# ControlBoardMain.net
KiCad netlist of a schematic drawn in EAGLE
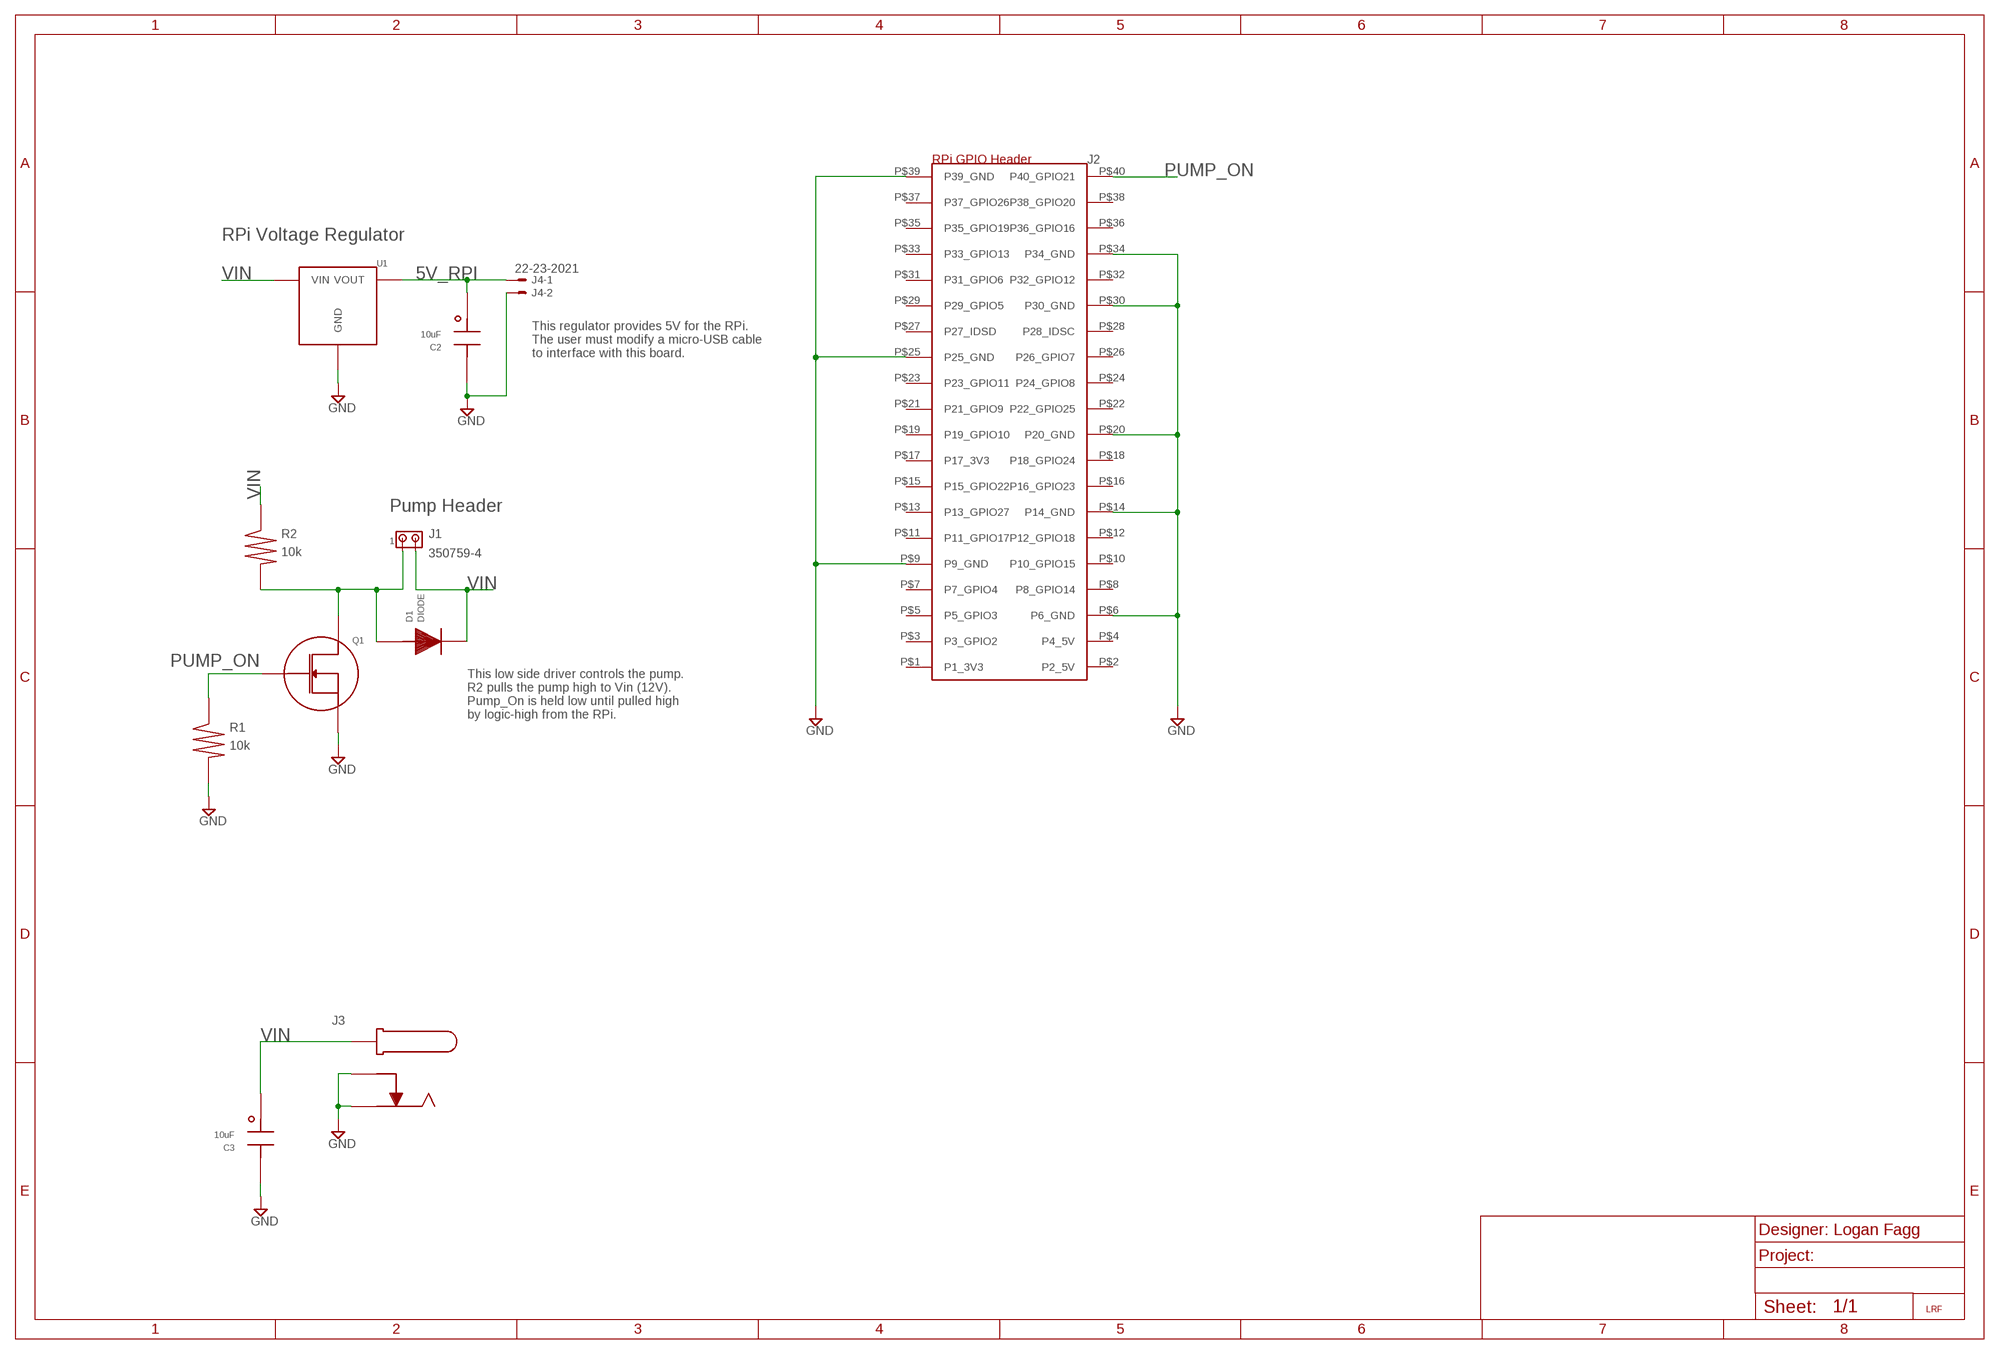
[diagram p0: schematic, sheet 1]

(export (version "E")
  (design (tool "Eeschema 10.0.6"))
  (components
    (comp (ref "C2")
      (value "10uF")
      (footprint "eagle-import:TH_PASSIVE")
      (libsource (lib "eagle-import") (part "CAPACITOR"))
    )
    (comp (ref "C3")
      (value "10uF")
      (footprint "eagle-import:TH_PASSIVE")
      (libsource (lib "eagle-import") (part "CAPACITOR"))
    )
    (comp (ref "D1")
      (value "DIODE")
      (footprint "eagle-import:TH_PASSIVE")
      (libsource (lib "eagle-import") (part "DIODE"))
    )
    (comp (ref "J1")
      (value "350759-4")
      (footprint "eagle-import:350759-4")
      (libsource (lib "eagle-import") (part "350759-4"))
    )
    (comp (ref "J2")
      (value "RPI_HEADER")
      (footprint "eagle-import:RPIHEADER")
      (libsource (lib "eagle-import") (part "RPI_HEADER"))
    )
    (comp (ref "J3")
      (value "DC_POWERJACK")
      (footprint "eagle-import:DC_POWERJACK")
      (libsource (lib "eagle-import") (part "DC_POWERJACK"))
    )
    (comp (ref "J4")
      (value "22-23-2021")
      (footprint "eagle-import:22-23-2021")
      (fields (field (name "MF") "MOLEX"))
      (libsource (lib "eagle-import") (part "22-23-2021"))
    )
    (comp (ref "Q1")
      (value "NMOS")
      (footprint "eagle-import:TH_3PIN")
      (libsource (lib "eagle-import") (part "NMOS"))
    )
    (comp (ref "R1")
      (value "10k")
      (footprint "eagle-import:TH_PASSIVE")
      (libsource (lib "eagle-import") (part "RESISTOR"))
    )
    (comp (ref "R2")
      (value "10k")
      (footprint "eagle-import:TH_PASSIVE")
      (libsource (lib "eagle-import") (part "RESISTOR"))
    )
    (comp (ref "U$1")
      (value "LOGO")
      (footprint "eagle-import:LOGO")
      (libsource (lib "eagle-import") (part "LOGO"))
    )
    (comp (ref "U1")
      (value "VOLTAGE_REGULATOR")
      (footprint "eagle-import:TH_3PIN")
      (libsource (lib "eagle-import") (part "VOLTAGE_REGULATOR"))
    )
  )
  (nets
    (net (code "1") (name "/5V_RPI") (class "Default")
      (node (ref "C2") (pin "P1") (pinfunction "P1_P1") (pintype "bidirectional"))
      (node (ref "J4") (pin "1") (pinfunction "S_1") (pintype "passive"))
      (node (ref "U1") (pin "P3") (pinfunction "VOUT_P3") (pintype "bidirectional"))
    )
    (net (code "2") (name "/PUMP_ON") (class "Default")
      (node (ref "J2") (pin "P$40") (pinfunction "P40_GPIO21_P$40") (pintype "bidirectional"))
      (node (ref "Q1") (pin "P1") (pinfunction "GATE_P1") (pintype "bidirectional"))
      (node (ref "R1") (pin "P1") (pinfunction "P1_P1") (pintype "bidirectional"))
    )
    (net (code "3") (name "/VIN") (class "Default")
      (node (ref "C3") (pin "P1") (pinfunction "P1_P1") (pintype "bidirectional"))
      (node (ref "D1") (pin "P1") (pinfunction "P1_P1") (pintype "bidirectional"))
      (node (ref "J1") (pin "2") (pinfunction "2_2") (pintype "passive"))
      (node (ref "J3") (pin "P1") (pinfunction "P1_P1") (pintype "bidirectional"))
      (node (ref "R2") (pin "P1") (pinfunction "P1_P1") (pintype "bidirectional"))
      (node (ref "U1") (pin "P1") (pinfunction "VIN_P1") (pintype "bidirectional"))
    )
    (net (code "4") (name "GND") (class "Default")
      (node (ref "C2") (pin "P2") (pinfunction "P2_P2") (pintype "bidirectional"))
      (node (ref "C3") (pin "P2") (pinfunction "P2_P2") (pintype "bidirectional"))
      (node (ref "J2") (pin "P$14") (pinfunction "P14_GND_P$14") (pintype "bidirectional"))
      (node (ref "J2") (pin "P$20") (pinfunction "P20_GND_P$20") (pintype "bidirectional"))
      (node (ref "J2") (pin "P$25") (pinfunction "P25_GND_P$25") (pintype "bidirectional"))
      (node (ref "J2") (pin "P$30") (pinfunction "P30_GND_P$30") (pintype "bidirectional"))
      (node (ref "J2") (pin "P$34") (pinfunction "P34_GND_P$34") (pintype "bidirectional"))
      (node (ref "J2") (pin "P$39") (pinfunction "P39_GND_P$39") (pintype "bidirectional"))
      (node (ref "J2") (pin "P$6") (pinfunction "P6_GND_P$6") (pintype "bidirectional"))
      (node (ref "J2") (pin "P$9") (pinfunction "P9_GND_P$9") (pintype "bidirectional"))
      (node (ref "J3") (pin "P2") (pinfunction "P2_P2") (pintype "bidirectional"))
      (node (ref "J3") (pin "P3") (pinfunction "P3_P3") (pintype "bidirectional"))
      (node (ref "J4") (pin "2") (pinfunction "S_2") (pintype "passive"))
      (node (ref "Q1") (pin "P3") (pinfunction "SOURCE_P3") (pintype "bidirectional"))
      (node (ref "R1") (pin "P2") (pinfunction "P2_P2") (pintype "bidirectional"))
      (node (ref "U1") (pin "P2") (pinfunction "GND_P2") (pintype "bidirectional"))
    )
    (net (code "5") (name "Net-(Q1-DRAIN)") (class "Default")
      (node (ref "D1") (pin "P2") (pinfunction "P2_P2") (pintype "bidirectional"))
      (node (ref "J1") (pin "1") (pinfunction "1_1") (pintype "passive"))
      (node (ref "Q1") (pin "P2") (pinfunction "DRAIN_P2") (pintype "bidirectional"))
      (node (ref "R2") (pin "P2") (pinfunction "P2_P2") (pintype "bidirectional"))
    )
    (net (code "6") (name "unconnected-(J2-P1_3V3-PadP$1)") (class "Default")
      (node (ref "J2") (pin "P$1") (pinfunction "P1_3V3_P$1") (pintype "bidirectional"))
    )
    (net (code "7") (name "unconnected-(J2-P2_5V-PadP$2)") (class "Default")
      (node (ref "J2") (pin "P$2") (pinfunction "P2_5V_P$2") (pintype "bidirectional"))
    )
    (net (code "8") (name "unconnected-(J2-P3_GPIO2-PadP$3)") (class "Default")
      (node (ref "J2") (pin "P$3") (pinfunction "P3_GPIO2_P$3") (pintype "bidirectional"))
    )
    (net (code "9") (name "unconnected-(J2-P4_5V-PadP$4)") (class "Default")
      (node (ref "J2") (pin "P$4") (pinfunction "P4_5V_P$4") (pintype "bidirectional"))
    )
    (net (code "10") (name "unconnected-(J2-P5_GPIO3-PadP$5)") (class "Default")
      (node (ref "J2") (pin "P$5") (pinfunction "P5_GPIO3_P$5") (pintype "bidirectional"))
    )
    (net (code "11") (name "unconnected-(J2-P7_GPIO4-PadP$7)") (class "Default")
      (node (ref "J2") (pin "P$7") (pinfunction "P7_GPIO4_P$7") (pintype "bidirectional"))
    )
    (net (code "12") (name "unconnected-(J2-P8_GPIO14-PadP$8)") (class "Default")
      (node (ref "J2") (pin "P$8") (pinfunction "P8_GPIO14_P$8") (pintype "bidirectional"))
    )
    (net (code "13") (name "unconnected-(J2-P10_GPIO15-PadP$10)") (class "Default")
      (node (ref "J2") (pin "P$10") (pinfunction "P10_GPIO15_P$10") (pintype "bidirectional"))
    )
    (net (code "14") (name "unconnected-(J2-P11_GPIO17-PadP$11)") (class "Default")
      (node (ref "J2") (pin "P$11") (pinfunction "P11_GPIO17_P$11") (pintype "bidirectional"))
    )
    (net (code "15") (name "unconnected-(J2-P12_GPIO18-PadP$12)") (class "Default")
      (node (ref "J2") (pin "P$12") (pinfunction "P12_GPIO18_P$12") (pintype "bidirectional"))
    )
    (net (code "16") (name "unconnected-(J2-P13_GPIO27-PadP$13)") (class "Default")
      (node (ref "J2") (pin "P$13") (pinfunction "P13_GPIO27_P$13") (pintype "bidirectional"))
    )
    (net (code "17") (name "unconnected-(J2-P15_GPIO22-PadP$15)") (class "Default")
      (node (ref "J2") (pin "P$15") (pinfunction "P15_GPIO22_P$15") (pintype "bidirectional"))
    )
    (net (code "18") (name "unconnected-(J2-P16_GPIO23-PadP$16)") (class "Default")
      (node (ref "J2") (pin "P$16") (pinfunction "P16_GPIO23_P$16") (pintype "bidirectional"))
    )
    (net (code "19") (name "unconnected-(J2-P17_3V3-PadP$17)") (class "Default")
      (node (ref "J2") (pin "P$17") (pinfunction "P17_3V3_P$17") (pintype "bidirectional"))
    )
    (net (code "20") (name "unconnected-(J2-P18_GPIO24-PadP$18)") (class "Default")
      (node (ref "J2") (pin "P$18") (pinfunction "P18_GPIO24_P$18") (pintype "bidirectional"))
    )
    (net (code "21") (name "unconnected-(J2-P19_GPIO10-PadP$19)") (class "Default")
      (node (ref "J2") (pin "P$19") (pinfunction "P19_GPIO10_P$19") (pintype "bidirectional"))
    )
    (net (code "22") (name "unconnected-(J2-P21_GPIO9-PadP$21)") (class "Default")
      (node (ref "J2") (pin "P$21") (pinfunction "P21_GPIO9_P$21") (pintype "bidirectional"))
    )
    (net (code "23") (name "unconnected-(J2-P22_GPIO25-PadP$22)") (class "Default")
      (node (ref "J2") (pin "P$22") (pinfunction "P22_GPIO25_P$22") (pintype "bidirectional"))
    )
    (net (code "24") (name "unconnected-(J2-P23_GPIO11-PadP$23)") (class "Default")
      (node (ref "J2") (pin "P$23") (pinfunction "P23_GPIO11_P$23") (pintype "bidirectional"))
    )
    (net (code "25") (name "unconnected-(J2-P24_GPIO8-PadP$24)") (class "Default")
      (node (ref "J2") (pin "P$24") (pinfunction "P24_GPIO8_P$24") (pintype "bidirectional"))
    )
    (net (code "26") (name "unconnected-(J2-P26_GPIO7-PadP$26)") (class "Default")
      (node (ref "J2") (pin "P$26") (pinfunction "P26_GPIO7_P$26") (pintype "bidirectional"))
    )
    (net (code "27") (name "unconnected-(J2-P27_IDSD-PadP$27)") (class "Default")
      (node (ref "J2") (pin "P$27") (pinfunction "P27_IDSD_P$27") (pintype "bidirectional"))
    )
    (net (code "28") (name "unconnected-(J2-P28_IDSC-PadP$28)") (class "Default")
      (node (ref "J2") (pin "P$28") (pinfunction "P28_IDSC_P$28") (pintype "bidirectional"))
    )
    (net (code "29") (name "unconnected-(J2-P29_GPIO5-PadP$29)") (class "Default")
      (node (ref "J2") (pin "P$29") (pinfunction "P29_GPIO5_P$29") (pintype "bidirectional"))
    )
    (net (code "30") (name "unconnected-(J2-P31_GPIO6-PadP$31)") (class "Default")
      (node (ref "J2") (pin "P$31") (pinfunction "P31_GPIO6_P$31") (pintype "bidirectional"))
    )
    (net (code "31") (name "unconnected-(J2-P32_GPIO12-PadP$32)") (class "Default")
      (node (ref "J2") (pin "P$32") (pinfunction "P32_GPIO12_P$32") (pintype "bidirectional"))
    )
    (net (code "32") (name "unconnected-(J2-P33_GPIO13-PadP$33)") (class "Default")
      (node (ref "J2") (pin "P$33") (pinfunction "P33_GPIO13_P$33") (pintype "bidirectional"))
    )
    (net (code "33") (name "unconnected-(J2-P35_GPIO19-PadP$35)") (class "Default")
      (node (ref "J2") (pin "P$35") (pinfunction "P35_GPIO19_P$35") (pintype "bidirectional"))
    )
    (net (code "34") (name "unconnected-(J2-P36_GPIO16-PadP$36)") (class "Default")
      (node (ref "J2") (pin "P$36") (pinfunction "P36_GPIO16_P$36") (pintype "bidirectional"))
    )
    (net (code "35") (name "unconnected-(J2-P37_GPIO26-PadP$37)") (class "Default")
      (node (ref "J2") (pin "P$37") (pinfunction "P37_GPIO26_P$37") (pintype "bidirectional"))
    )
    (net (code "36") (name "unconnected-(J2-P38_GPIO20-PadP$38)") (class "Default")
      (node (ref "J2") (pin "P$38") (pinfunction "P38_GPIO20_P$38") (pintype "bidirectional"))
    )
  )
)
